# pump_driver.net
KiCad netlist of a schematic drawn in EAGLE
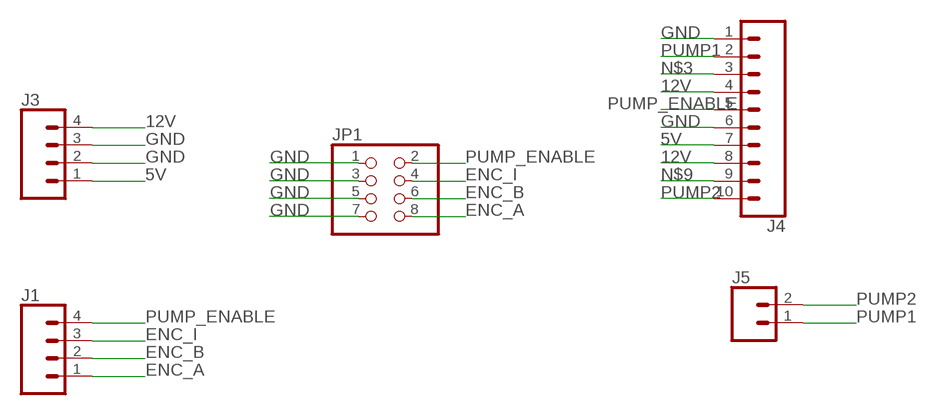
[diagram p0: schematic, sheet 1]

(export (version "E")
  (design (tool "Eeschema 10.0.6"))
  (components
    (comp (ref "J1")
      (value "CONN_04")
      (footprint "eagle-import:1X04")
      (libsource (lib "eagle-import") (part "CONN_04"))
    )
    (comp (ref "J3")
      (value "CONN_04")
      (footprint "eagle-import:1X04")
      (libsource (lib "eagle-import") (part "CONN_04"))
    )
    (comp (ref "J4")
      (value "CONN_10\"")
      (footprint "eagle-import:1X10")
      (libsource (lib "eagle-import") (part "CONN_10{dblquote}"))
    )
    (comp (ref "J5")
      (value "CONN_02")
      (footprint "eagle-import:1X02")
      (libsource (lib "eagle-import") (part "CONN_02"))
    )
    (comp (ref "JP1")
      (value "PINHD-2X4")
      (footprint "eagle-import:2X04")
      (libsource (lib "eagle-import") (part "PINHD-2X4"))
    )
  )
  (nets
    (net (code "1") (name "/5V") (class "Default")
      (node (ref "J3") (pin "1") (pinfunction "1_1") (pintype "passive"))
      (node (ref "J4") (pin "7") (pinfunction "7_7") (pintype "passive"))
    )
    (net (code "2") (name "/12V") (class "Default")
      (node (ref "J3") (pin "4") (pinfunction "4_4") (pintype "passive"))
      (node (ref "J4") (pin "4") (pinfunction "4_4") (pintype "passive"))
      (node (ref "J4") (pin "8") (pinfunction "8_8") (pintype "passive"))
    )
    (net (code "3") (name "/ENC_A") (class "Default")
      (node (ref "J1") (pin "1") (pinfunction "1_1") (pintype "passive"))
      (node (ref "JP1") (pin "8") (pinfunction "8_8") (pintype "passive"))
    )
    (net (code "4") (name "/ENC_B") (class "Default")
      (node (ref "J1") (pin "2") (pinfunction "2_2") (pintype "passive"))
      (node (ref "JP1") (pin "6") (pinfunction "6_6") (pintype "passive"))
    )
    (net (code "5") (name "/ENC_I") (class "Default")
      (node (ref "J1") (pin "3") (pinfunction "3_3") (pintype "passive"))
      (node (ref "JP1") (pin "4") (pinfunction "4_4") (pintype "passive"))
    )
    (net (code "6") (name "/GND") (class "Default")
      (node (ref "J3") (pin "2") (pinfunction "2_2") (pintype "passive"))
      (node (ref "J3") (pin "3") (pinfunction "3_3") (pintype "passive"))
      (node (ref "J4") (pin "1") (pinfunction "1_1") (pintype "passive"))
      (node (ref "J4") (pin "6") (pinfunction "6_6") (pintype "passive"))
      (node (ref "JP1") (pin "1") (pinfunction "1_1") (pintype "passive"))
      (node (ref "JP1") (pin "3") (pinfunction "3_3") (pintype "passive"))
      (node (ref "JP1") (pin "5") (pinfunction "5_5") (pintype "passive"))
      (node (ref "JP1") (pin "7") (pinfunction "7_7") (pintype "passive"))
    )
    (net (code "7") (name "/N$3") (class "Default")
      (node (ref "J4") (pin "3") (pinfunction "3_3") (pintype "passive"))
    )
    (net (code "8") (name "/N$9") (class "Default")
      (node (ref "J4") (pin "9") (pinfunction "9_9") (pintype "passive"))
    )
    (net (code "9") (name "/PUMP1") (class "Default")
      (node (ref "J4") (pin "2") (pinfunction "2_2") (pintype "passive"))
      (node (ref "J5") (pin "1") (pinfunction "1_1") (pintype "passive"))
    )
    (net (code "10") (name "/PUMP2") (class "Default")
      (node (ref "J4") (pin "10") (pinfunction "10_10") (pintype "passive"))
      (node (ref "J5") (pin "2") (pinfunction "2_2") (pintype "passive"))
    )
    (net (code "11") (name "/PUMP_ENABLE") (class "Default")
      (node (ref "J1") (pin "4") (pinfunction "4_4") (pintype "passive"))
      (node (ref "J4") (pin "5") (pinfunction "5_5") (pintype "passive"))
      (node (ref "JP1") (pin "2") (pinfunction "2_2") (pintype "passive"))
    )
  )
)
